# GPSClock_Display.net
KiCad netlist of a schematic drawn in EAGLE
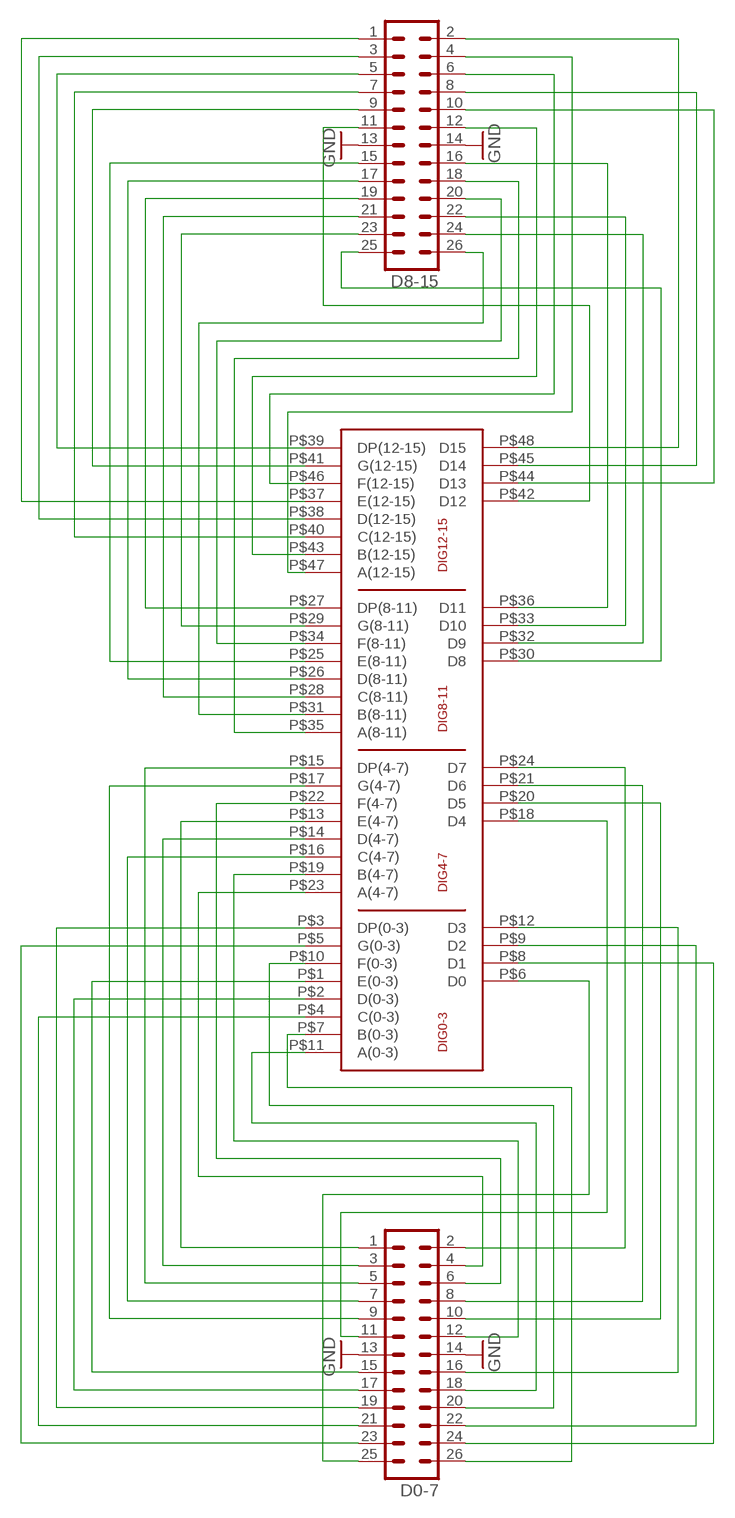
[diagram p0: schematic, sheet 1]

(export (version "E")
  (design (tool "Eeschema 10.0.6"))
  (components
    (comp (ref "D0-7")
      (value "MA13-2")
      (footprint "eagle-import:MA13-2")
      (libsource (lib "eagle-import") (part "MA13-2"))
    )
    (comp (ref "D8-15")
      (value "MA13-2")
      (footprint "eagle-import:MA13-2")
      (libsource (lib "eagle-import") (part "MA13-2"))
    )
    (comp (ref "U$1")
      (value "4X7X4_SEG")
      (footprint "eagle-import:4X7X4_SEG")
      (libsource (lib "eagle-import") (part "4X7X4_SEG"))
    )
  )
  (nets
    (net (code "1") (name "GND") (class "Default")
      (node (ref "D0-7") (pin "13") (pinfunction "13_13") (pintype "passive"))
      (node (ref "D0-7") (pin "14") (pinfunction "14_14") (pintype "passive"))
      (node (ref "D8-15") (pin "13") (pinfunction "13_13") (pintype "passive"))
      (node (ref "D8-15") (pin "14") (pinfunction "14_14") (pintype "passive"))
    )
    (net (code "2") (name "Net-(U$1-A(0-3))") (class "Default")
      (node (ref "D0-7") (pin "18") (pinfunction "18_18") (pintype "passive"))
      (node (ref "U$1") (pin "P$11") (pinfunction "A(0-3)_P$11") (pintype "bidirectional"))
    )
    (net (code "3") (name "Net-(U$1-A(4-7))") (class "Default")
      (node (ref "D0-7") (pin "4") (pinfunction "4_4") (pintype "passive"))
      (node (ref "U$1") (pin "P$23") (pinfunction "A(4-7)_P$23") (pintype "bidirectional"))
    )
    (net (code "4") (name "Net-(U$1-A(8-11))") (class "Default")
      (node (ref "D8-15") (pin "18") (pinfunction "18_18") (pintype "passive"))
      (node (ref "U$1") (pin "P$35") (pinfunction "A(8-11)_P$35") (pintype "bidirectional"))
    )
    (net (code "5") (name "Net-(U$1-A(12-15))") (class "Default")
      (node (ref "D8-15") (pin "4") (pinfunction "4_4") (pintype "passive"))
      (node (ref "U$1") (pin "P$47") (pinfunction "A(12-15)_P$47") (pintype "bidirectional"))
    )
    (net (code "6") (name "Net-(U$1-B(0-3))") (class "Default")
      (node (ref "D0-7") (pin "26") (pinfunction "26_26") (pintype "passive"))
      (node (ref "U$1") (pin "P$7") (pinfunction "B(0-3)_P$7") (pintype "bidirectional"))
    )
    (net (code "7") (name "Net-(U$1-B(4-7))") (class "Default")
      (node (ref "D0-7") (pin "12") (pinfunction "12_12") (pintype "passive"))
      (node (ref "U$1") (pin "P$19") (pinfunction "B(4-7)_P$19") (pintype "bidirectional"))
    )
    (net (code "8") (name "Net-(U$1-B(8-11))") (class "Default")
      (node (ref "D8-15") (pin "26") (pinfunction "26_26") (pintype "passive"))
      (node (ref "U$1") (pin "P$31") (pinfunction "B(8-11)_P$31") (pintype "bidirectional"))
    )
    (net (code "9") (name "Net-(U$1-B(12-15))") (class "Default")
      (node (ref "D8-15") (pin "12") (pinfunction "12_12") (pintype "passive"))
      (node (ref "U$1") (pin "P$43") (pinfunction "B(12-15)_P$43") (pintype "bidirectional"))
    )
    (net (code "10") (name "Net-(U$1-C(0-3))") (class "Default")
      (node (ref "D0-7") (pin "21") (pinfunction "21_21") (pintype "passive"))
      (node (ref "U$1") (pin "P$4") (pinfunction "C(0-3)_P$4") (pintype "bidirectional"))
    )
    (net (code "11") (name "Net-(U$1-C(4-7))") (class "Default")
      (node (ref "D0-7") (pin "7") (pinfunction "7_7") (pintype "passive"))
      (node (ref "U$1") (pin "P$16") (pinfunction "C(4-7)_P$16") (pintype "bidirectional"))
    )
    (net (code "12") (name "Net-(U$1-C(8-11))") (class "Default")
      (node (ref "D8-15") (pin "21") (pinfunction "21_21") (pintype "passive"))
      (node (ref "U$1") (pin "P$28") (pinfunction "C(8-11)_P$28") (pintype "bidirectional"))
    )
    (net (code "13") (name "Net-(U$1-C(12-15))") (class "Default")
      (node (ref "D8-15") (pin "7") (pinfunction "7_7") (pintype "passive"))
      (node (ref "U$1") (pin "P$40") (pinfunction "C(12-15)_P$40") (pintype "bidirectional"))
    )
    (net (code "14") (name "Net-(U$1-D(0-3))") (class "Default")
      (node (ref "D0-7") (pin "17") (pinfunction "17_17") (pintype "passive"))
      (node (ref "U$1") (pin "P$2") (pinfunction "D(0-3)_P$2") (pintype "bidirectional"))
    )
    (net (code "15") (name "Net-(U$1-D(4-7))") (class "Default")
      (node (ref "D0-7") (pin "3") (pinfunction "3_3") (pintype "passive"))
      (node (ref "U$1") (pin "P$14") (pinfunction "D(4-7)_P$14") (pintype "bidirectional"))
    )
    (net (code "16") (name "Net-(U$1-D(8-11))") (class "Default")
      (node (ref "D8-15") (pin "17") (pinfunction "17_17") (pintype "passive"))
      (node (ref "U$1") (pin "P$26") (pinfunction "D(8-11)_P$26") (pintype "bidirectional"))
    )
    (net (code "17") (name "Net-(U$1-D(12-15))") (class "Default")
      (node (ref "D8-15") (pin "3") (pinfunction "3_3") (pintype "passive"))
      (node (ref "U$1") (pin "P$38") (pinfunction "D(12-15)_P$38") (pintype "bidirectional"))
    )
    (net (code "18") (name "Net-(U$1-D0)") (class "Default")
      (node (ref "D0-7") (pin "25") (pinfunction "25_25") (pintype "passive"))
      (node (ref "U$1") (pin "P$6") (pinfunction "D0_P$6") (pintype "bidirectional"))
    )
    (net (code "19") (name "Net-(U$1-D1)") (class "Default")
      (node (ref "D0-7") (pin "24") (pinfunction "24_24") (pintype "passive"))
      (node (ref "U$1") (pin "P$8") (pinfunction "D1_P$8") (pintype "bidirectional"))
    )
    (net (code "20") (name "Net-(U$1-D2)") (class "Default")
      (node (ref "D0-7") (pin "22") (pinfunction "22_22") (pintype "passive"))
      (node (ref "U$1") (pin "P$9") (pinfunction "D2_P$9") (pintype "bidirectional"))
    )
    (net (code "21") (name "Net-(U$1-D3)") (class "Default")
      (node (ref "D0-7") (pin "16") (pinfunction "16_16") (pintype "passive"))
      (node (ref "U$1") (pin "P$12") (pinfunction "D3_P$12") (pintype "bidirectional"))
    )
    (net (code "22") (name "Net-(U$1-D4)") (class "Default")
      (node (ref "D0-7") (pin "11") (pinfunction "11_11") (pintype "passive"))
      (node (ref "U$1") (pin "P$18") (pinfunction "D4_P$18") (pintype "bidirectional"))
    )
    (net (code "23") (name "Net-(U$1-D5)") (class "Default")
      (node (ref "D0-7") (pin "10") (pinfunction "10_10") (pintype "passive"))
      (node (ref "U$1") (pin "P$20") (pinfunction "D5_P$20") (pintype "bidirectional"))
    )
    (net (code "24") (name "Net-(U$1-D6)") (class "Default")
      (node (ref "D0-7") (pin "8") (pinfunction "8_8") (pintype "passive"))
      (node (ref "U$1") (pin "P$21") (pinfunction "D6_P$21") (pintype "bidirectional"))
    )
    (net (code "25") (name "Net-(U$1-D7)") (class "Default")
      (node (ref "D0-7") (pin "2") (pinfunction "2_2") (pintype "passive"))
      (node (ref "U$1") (pin "P$24") (pinfunction "D7_P$24") (pintype "bidirectional"))
    )
    (net (code "26") (name "Net-(U$1-D8)") (class "Default")
      (node (ref "D8-15") (pin "25") (pinfunction "25_25") (pintype "passive"))
      (node (ref "U$1") (pin "P$30") (pinfunction "D8_P$30") (pintype "bidirectional"))
    )
    (net (code "27") (name "Net-(U$1-D9)") (class "Default")
      (node (ref "D8-15") (pin "24") (pinfunction "24_24") (pintype "passive"))
      (node (ref "U$1") (pin "P$32") (pinfunction "D9_P$32") (pintype "bidirectional"))
    )
    (net (code "28") (name "Net-(U$1-D10)") (class "Default")
      (node (ref "D8-15") (pin "22") (pinfunction "22_22") (pintype "passive"))
      (node (ref "U$1") (pin "P$33") (pinfunction "D10_P$33") (pintype "bidirectional"))
    )
    (net (code "29") (name "Net-(U$1-D11)") (class "Default")
      (node (ref "D8-15") (pin "16") (pinfunction "16_16") (pintype "passive"))
      (node (ref "U$1") (pin "P$36") (pinfunction "D11_P$36") (pintype "bidirectional"))
    )
    (net (code "30") (name "Net-(U$1-D12)") (class "Default")
      (node (ref "D8-15") (pin "11") (pinfunction "11_11") (pintype "passive"))
      (node (ref "U$1") (pin "P$42") (pinfunction "D12_P$42") (pintype "bidirectional"))
    )
    (net (code "31") (name "Net-(U$1-D13)") (class "Default")
      (node (ref "D8-15") (pin "10") (pinfunction "10_10") (pintype "passive"))
      (node (ref "U$1") (pin "P$44") (pinfunction "D13_P$44") (pintype "bidirectional"))
    )
    (net (code "32") (name "Net-(U$1-D14)") (class "Default")
      (node (ref "D8-15") (pin "8") (pinfunction "8_8") (pintype "passive"))
      (node (ref "U$1") (pin "P$45") (pinfunction "D14_P$45") (pintype "bidirectional"))
    )
    (net (code "33") (name "Net-(U$1-D15)") (class "Default")
      (node (ref "D8-15") (pin "2") (pinfunction "2_2") (pintype "passive"))
      (node (ref "U$1") (pin "P$48") (pinfunction "D15_P$48") (pintype "bidirectional"))
    )
    (net (code "34") (name "Net-(U$1-DP(0-3))") (class "Default")
      (node (ref "D0-7") (pin "19") (pinfunction "19_19") (pintype "passive"))
      (node (ref "U$1") (pin "P$3") (pinfunction "DP(0-3)_P$3") (pintype "bidirectional"))
    )
    (net (code "35") (name "Net-(U$1-DP(4-7))") (class "Default")
      (node (ref "D0-7") (pin "5") (pinfunction "5_5") (pintype "passive"))
      (node (ref "U$1") (pin "P$15") (pinfunction "DP(4-7)_P$15") (pintype "bidirectional"))
    )
    (net (code "36") (name "Net-(U$1-DP(8-11))") (class "Default")
      (node (ref "D8-15") (pin "19") (pinfunction "19_19") (pintype "passive"))
      (node (ref "U$1") (pin "P$27") (pinfunction "DP(8-11)_P$27") (pintype "bidirectional"))
    )
    (net (code "37") (name "Net-(U$1-DP(12-15))") (class "Default")
      (node (ref "D8-15") (pin "5") (pinfunction "5_5") (pintype "passive"))
      (node (ref "U$1") (pin "P$39") (pinfunction "DP(12-15)_P$39") (pintype "bidirectional"))
    )
    (net (code "38") (name "Net-(U$1-E(0-3))") (class "Default")
      (node (ref "D0-7") (pin "15") (pinfunction "15_15") (pintype "passive"))
      (node (ref "U$1") (pin "P$1") (pinfunction "E(0-3)_P$1") (pintype "bidirectional"))
    )
    (net (code "39") (name "Net-(U$1-E(4-7))") (class "Default")
      (node (ref "D0-7") (pin "1") (pinfunction "1_1") (pintype "passive"))
      (node (ref "U$1") (pin "P$13") (pinfunction "E(4-7)_P$13") (pintype "bidirectional"))
    )
    (net (code "40") (name "Net-(U$1-E(8-11))") (class "Default")
      (node (ref "D8-15") (pin "15") (pinfunction "15_15") (pintype "passive"))
      (node (ref "U$1") (pin "P$25") (pinfunction "E(8-11)_P$25") (pintype "bidirectional"))
    )
    (net (code "41") (name "Net-(U$1-E(12-15))") (class "Default")
      (node (ref "D8-15") (pin "1") (pinfunction "1_1") (pintype "passive"))
      (node (ref "U$1") (pin "P$37") (pinfunction "E(12-15)_P$37") (pintype "bidirectional"))
    )
    (net (code "42") (name "Net-(U$1-F(0-3))") (class "Default")
      (node (ref "D0-7") (pin "20") (pinfunction "20_20") (pintype "passive"))
      (node (ref "U$1") (pin "P$10") (pinfunction "F(0-3)_P$10") (pintype "bidirectional"))
    )
    (net (code "43") (name "Net-(U$1-F(4-7))") (class "Default")
      (node (ref "D0-7") (pin "6") (pinfunction "6_6") (pintype "passive"))
      (node (ref "U$1") (pin "P$22") (pinfunction "F(4-7)_P$22") (pintype "bidirectional"))
    )
    (net (code "44") (name "Net-(U$1-F(8-11))") (class "Default")
      (node (ref "D8-15") (pin "20") (pinfunction "20_20") (pintype "passive"))
      (node (ref "U$1") (pin "P$34") (pinfunction "F(8-11)_P$34") (pintype "bidirectional"))
    )
    (net (code "45") (name "Net-(U$1-F(12-15))") (class "Default")
      (node (ref "D8-15") (pin "6") (pinfunction "6_6") (pintype "passive"))
      (node (ref "U$1") (pin "P$46") (pinfunction "F(12-15)_P$46") (pintype "bidirectional"))
    )
    (net (code "46") (name "Net-(U$1-G(0-3))") (class "Default")
      (node (ref "D0-7") (pin "23") (pinfunction "23_23") (pintype "passive"))
      (node (ref "U$1") (pin "P$5") (pinfunction "G(0-3)_P$5") (pintype "bidirectional"))
    )
    (net (code "47") (name "Net-(U$1-G(4-7))") (class "Default")
      (node (ref "D0-7") (pin "9") (pinfunction "9_9") (pintype "passive"))
      (node (ref "U$1") (pin "P$17") (pinfunction "G(4-7)_P$17") (pintype "bidirectional"))
    )
    (net (code "48") (name "Net-(U$1-G(8-11))") (class "Default")
      (node (ref "D8-15") (pin "23") (pinfunction "23_23") (pintype "passive"))
      (node (ref "U$1") (pin "P$29") (pinfunction "G(8-11)_P$29") (pintype "bidirectional"))
    )
    (net (code "49") (name "Net-(U$1-G(12-15))") (class "Default")
      (node (ref "D8-15") (pin "9") (pinfunction "9_9") (pintype "passive"))
      (node (ref "U$1") (pin "P$41") (pinfunction "G(12-15)_P$41") (pintype "bidirectional"))
    )
  )
)
